# Pwdr-Circuit-0_1.net
KiCad netlist of a schematic drawn in EAGLE
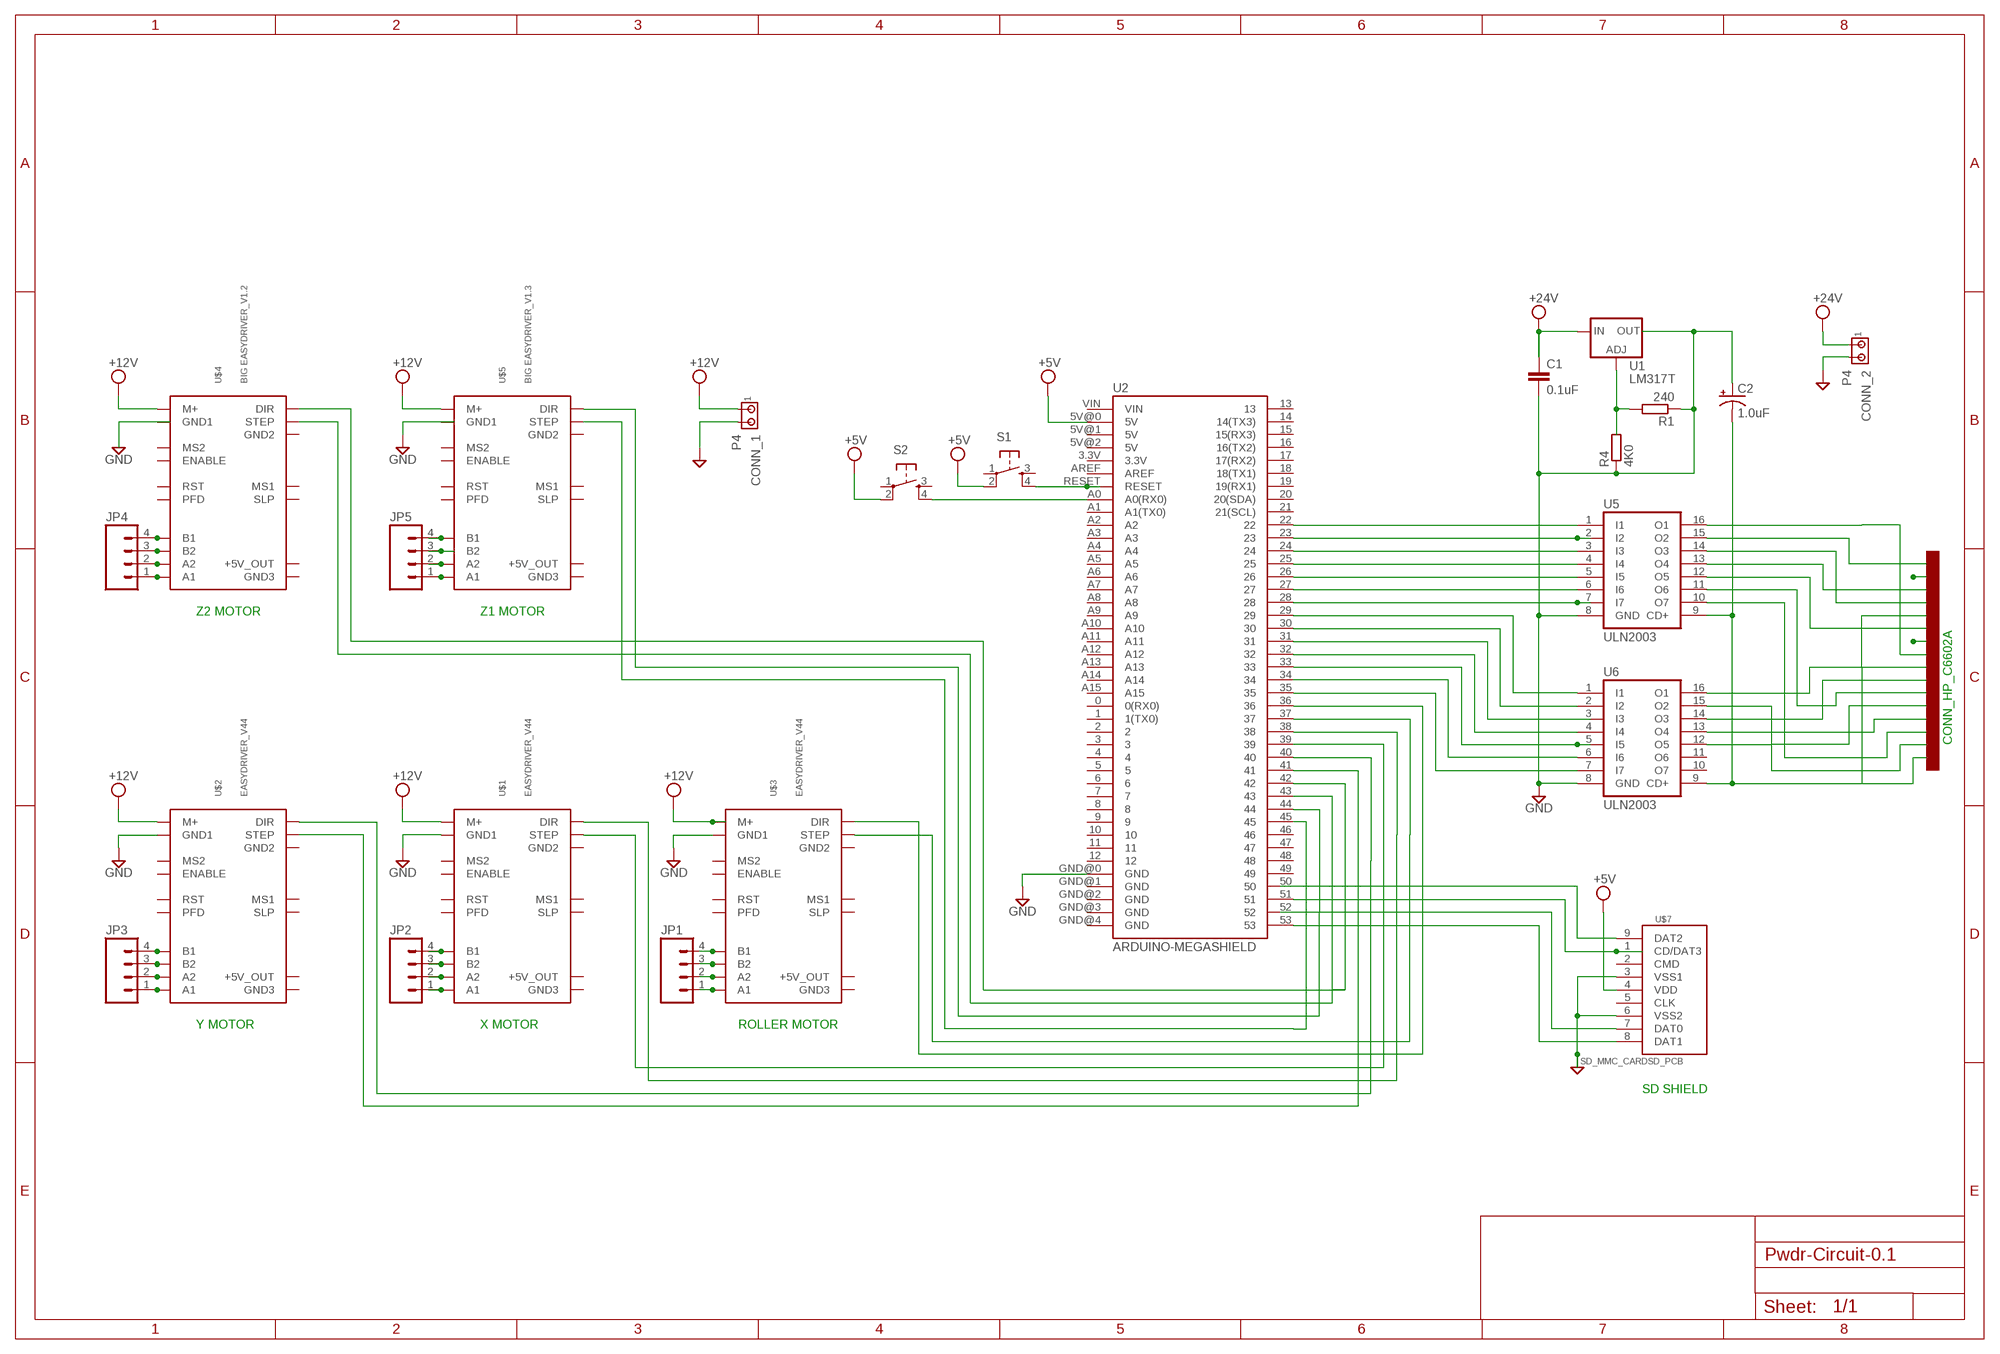
[diagram p0: schematic, sheet 1]

(export (version "E")
  (design (tool "Eeschema 10.0.6"))
  (components
    (comp (ref "C1")
      (value "0.1uF")
      (footprint "eagle-import:C025-024X044")
      (libsource (lib "eagle-import") (part "C-EU025-024X044"))
    )
    (comp (ref "C2")
      (value "1.0uF")
      (footprint "eagle-import:085CS_1AR")
      (libsource (lib "eagle-import") (part "CPOL-US085CS-1AR"))
    )
    (comp (ref "CONN_1")
      (value "P4")
      (footprint "eagle-import:1X2MTA")
      (libsource (lib "eagle-import") (part "MTA02-156"))
    )
    (comp (ref "CONN_2")
      (value "P4")
      (footprint "eagle-import:1X2MTA")
      (libsource (lib "eagle-import") (part "MTA02-156"))
    )
    (comp (ref "JP1")
      (value "M041X04_NO_SILK")
      (footprint "eagle-import:1X04_NO_SILK")
      (libsource (lib "eagle-import") (part "M041X04_NO_SILK"))
    )
    (comp (ref "JP2")
      (value "M041X04_NO_SILK")
      (footprint "eagle-import:1X04_NO_SILK")
      (libsource (lib "eagle-import") (part "M041X04_NO_SILK"))
    )
    (comp (ref "JP3")
      (value "M041X04_NO_SILK")
      (footprint "eagle-import:1X04_NO_SILK")
      (libsource (lib "eagle-import") (part "M041X04_NO_SILK"))
    )
    (comp (ref "JP4")
      (value "M041X04_NO_SILK")
      (footprint "eagle-import:1X04_NO_SILK")
      (libsource (lib "eagle-import") (part "M041X04_NO_SILK"))
    )
    (comp (ref "JP5")
      (value "M041X04_NO_SILK")
      (footprint "eagle-import:1X04_NO_SILK")
      (libsource (lib "eagle-import") (part "M041X04_NO_SILK"))
    )
    (comp (ref "R1")
      (value "240")
      (footprint "eagle-import:0204V")
      (libsource (lib "eagle-import") (part "R-EU_0204/2V"))
    )
    (comp (ref "R4")
      (value "4K0")
      (footprint "eagle-import:0204V")
      (libsource (lib "eagle-import") (part "R-EU_0204/2V"))
    )
    (comp (ref "S1")
      (value "TAC_SWITCHSMD")
      (footprint "eagle-import:TACTILE_SWITCH_SMD")
      (libsource (lib "eagle-import") (part "TAC_SWITCHSMD"))
    )
    (comp (ref "S2")
      (value "TAC_SWITCHSMD")
      (footprint "eagle-import:TACTILE_SWITCH_SMD")
      (libsource (lib "eagle-import") (part "TAC_SWITCHSMD"))
    )
    (comp (ref "U$1")
      (value "EASYDRIVER_V44")
      (footprint "eagle-import:EASYDRIVER_V44")
      (libsource (lib "eagle-import") (part "EASYDRIVER_V44"))
    )
    (comp (ref "U$2")
      (value "EASYDRIVER_V44")
      (footprint "eagle-import:EASYDRIVER_V44")
      (libsource (lib "eagle-import") (part "EASYDRIVER_V44"))
    )
    (comp (ref "U$3")
      (value "EASYDRIVER_V44")
      (footprint "eagle-import:EASYDRIVER_V44")
      (libsource (lib "eagle-import") (part "EASYDRIVER_V44"))
    )
    (comp (ref "U$4")
      (value "BIG EASYDRIVER_V1.2")
      (footprint "eagle-import:EASYDRIVER_V44")
      (libsource (lib "eagle-import") (part "EASYDRIVER_V44"))
    )
    (comp (ref "U$5")
      (value "BIG EASYDRIVER_V1.3")
      (footprint "eagle-import:EASYDRIVER_V44")
      (libsource (lib "eagle-import") (part "EASYDRIVER_V44"))
    )
    (comp (ref "U$7")
      (value "SD_MMC_CARDSD_PCB")
      (footprint "eagle-import:SD-MMC-CARD")
      (libsource (lib "eagle-import") (part "SD_MMC_CARDSD_PCB"))
    )
    (comp (ref "U1")
      (value "LM317T")
      (footprint "eagle-import:317L")
      (libsource (lib "eagle-import") (part "LM317L"))
    )
    (comp (ref "U2")
      (value "ARDUINO-MEGASHIELD")
      (footprint "eagle-import:ARDUINO_MEGA")
      (libsource (lib "eagle-import") (part "ARDUINO-MEGAFULL"))
    )
    (comp (ref "U5")
      (value "ULN2003")
      (footprint "eagle-import:DIL16")
      (libsource (lib "eagle-import") (part "ULN2003AN"))
    )
    (comp (ref "U6")
      (value "ULN2003")
      (footprint "eagle-import:DIL16")
      (libsource (lib "eagle-import") (part "ULN2003AN"))
    )
  )
  (nets
    (net (code "1") (name "+12V") (class "Default")
      (node (ref "C1") (pin "1") (pinfunction "1_1") (pintype "passive"))
      (node (ref "CONN_1") (pin "1") (pinfunction "1_1") (pintype "passive"))
      (node (ref "CONN_2") (pin "1") (pinfunction "1_1") (pintype "passive"))
      (node (ref "S1") (pin "2") (pinfunction "2_2") (pintype "passive"))
      (node (ref "S2") (pin "2") (pinfunction "2_2") (pintype "passive"))
      (node (ref "U$1") (pin "M+") (pinfunction "M+_M+") (pintype "bidirectional"))
      (node (ref "U$2") (pin "M+") (pinfunction "M+_M+") (pintype "bidirectional"))
      (node (ref "U$3") (pin "M+") (pinfunction "M+_M+") (pintype "bidirectional"))
      (node (ref "U$4") (pin "M+") (pinfunction "M+_M+") (pintype "bidirectional"))
      (node (ref "U$5") (pin "M+") (pinfunction "M+_M+") (pintype "bidirectional"))
      (node (ref "U$7") (pin "4") (pinfunction "VDD_4") (pintype "bidirectional"))
      (node (ref "U1") (pin "3") (pinfunction "IN_3") (pintype "input"))
      (node (ref "U2") (pin "5V@0") (pinfunction "5V_5V@0") (pintype "bidirectional"))
    )
    (net (code "2") (name "AGND") (class "Default")
      (node (ref "C1") (pin "2") (pinfunction "2_2") (pintype "passive"))
      (node (ref "C2") (pin "+") (pinfunction "+_+") (pintype "passive"))
      (node (ref "CONN_1") (pin "2") (pinfunction "2_2") (pintype "passive"))
      (node (ref "CONN_2") (pin "2") (pinfunction "2_2") (pintype "passive"))
      (node (ref "R1") (pin "1") (pinfunction "1_1") (pintype "passive"))
      (node (ref "R4") (pin "1") (pinfunction "1_1") (pintype "passive"))
      (node (ref "U$1") (pin "GND1") (pinfunction "GND1_GND1") (pintype "bidirectional"))
      (node (ref "U$2") (pin "GND1") (pinfunction "GND1_GND1") (pintype "bidirectional"))
      (node (ref "U$3") (pin "GND1") (pinfunction "GND1_GND1") (pintype "bidirectional"))
      (node (ref "U$4") (pin "GND1") (pinfunction "GND1_GND1") (pintype "bidirectional"))
      (node (ref "U$5") (pin "GND1") (pinfunction "GND1_GND1") (pintype "bidirectional"))
      (node (ref "U$7") (pin "3") (pinfunction "VSS1_3") (pintype "bidirectional"))
      (node (ref "U$7") (pin "6") (pinfunction "VSS2_6") (pintype "bidirectional"))
      (node (ref "U1") (pin "2") (pinfunction "OUT_2") (pintype "passive"))
      (node (ref "U2") (pin "GND@0") (pinfunction "GND_GND@0") (pintype "bidirectional"))
      (node (ref "U5") (pin "8") (pinfunction "GND_8") (pintype "power_in"))
      (node (ref "U6") (pin "8") (pinfunction "GND_8") (pintype "power_in"))
    )
    (net (code "3") (name "Net-(JP1-Pad1)") (class "Default")
      (node (ref "JP1") (pin "1") (pinfunction "1_1") (pintype "passive"))
      (node (ref "U$3") (pin "A1") (pinfunction "A1_A1") (pintype "bidirectional"))
    )
    (net (code "4") (name "Net-(JP1-Pad2)") (class "Default")
      (node (ref "JP1") (pin "2") (pinfunction "2_2") (pintype "passive"))
      (node (ref "U$3") (pin "A2") (pinfunction "A2_A2") (pintype "bidirectional"))
    )
    (net (code "5") (name "Net-(JP1-Pad3)") (class "Default")
      (node (ref "JP1") (pin "3") (pinfunction "3_3") (pintype "passive"))
      (node (ref "U$3") (pin "B2") (pinfunction "B2_B2") (pintype "bidirectional"))
    )
    (net (code "6") (name "Net-(JP1-Pad4)") (class "Default")
      (node (ref "JP1") (pin "4") (pinfunction "4_4") (pintype "passive"))
      (node (ref "U$3") (pin "B1") (pinfunction "B1_B1") (pintype "bidirectional"))
    )
    (net (code "7") (name "Net-(JP2-Pad1)") (class "Default")
      (node (ref "JP2") (pin "1") (pinfunction "1_1") (pintype "passive"))
      (node (ref "U$1") (pin "A1") (pinfunction "A1_A1") (pintype "bidirectional"))
    )
    (net (code "8") (name "Net-(JP2-Pad2)") (class "Default")
      (node (ref "JP2") (pin "2") (pinfunction "2_2") (pintype "passive"))
      (node (ref "U$1") (pin "A2") (pinfunction "A2_A2") (pintype "bidirectional"))
    )
    (net (code "9") (name "Net-(JP2-Pad3)") (class "Default")
      (node (ref "JP2") (pin "3") (pinfunction "3_3") (pintype "passive"))
      (node (ref "U$1") (pin "B2") (pinfunction "B2_B2") (pintype "bidirectional"))
    )
    (net (code "10") (name "Net-(JP2-Pad4)") (class "Default")
      (node (ref "JP2") (pin "4") (pinfunction "4_4") (pintype "passive"))
      (node (ref "U$1") (pin "B1") (pinfunction "B1_B1") (pintype "bidirectional"))
    )
    (net (code "11") (name "Net-(JP3-Pad1)") (class "Default")
      (node (ref "JP3") (pin "1") (pinfunction "1_1") (pintype "passive"))
      (node (ref "U$2") (pin "A1") (pinfunction "A1_A1") (pintype "bidirectional"))
    )
    (net (code "12") (name "Net-(JP3-Pad2)") (class "Default")
      (node (ref "JP3") (pin "2") (pinfunction "2_2") (pintype "passive"))
      (node (ref "U$2") (pin "A2") (pinfunction "A2_A2") (pintype "bidirectional"))
    )
    (net (code "13") (name "Net-(JP3-Pad3)") (class "Default")
      (node (ref "JP3") (pin "3") (pinfunction "3_3") (pintype "passive"))
      (node (ref "U$2") (pin "B2") (pinfunction "B2_B2") (pintype "bidirectional"))
    )
    (net (code "14") (name "Net-(JP3-Pad4)") (class "Default")
      (node (ref "JP3") (pin "4") (pinfunction "4_4") (pintype "passive"))
      (node (ref "U$2") (pin "B1") (pinfunction "B1_B1") (pintype "bidirectional"))
    )
    (net (code "15") (name "Net-(JP4-Pad1)") (class "Default")
      (node (ref "JP4") (pin "1") (pinfunction "1_1") (pintype "passive"))
      (node (ref "U$4") (pin "A1") (pinfunction "A1_A1") (pintype "bidirectional"))
    )
    (net (code "16") (name "Net-(JP4-Pad2)") (class "Default")
      (node (ref "JP4") (pin "2") (pinfunction "2_2") (pintype "passive"))
      (node (ref "U$4") (pin "A2") (pinfunction "A2_A2") (pintype "bidirectional"))
    )
    (net (code "17") (name "Net-(JP4-Pad3)") (class "Default")
      (node (ref "JP4") (pin "3") (pinfunction "3_3") (pintype "passive"))
      (node (ref "U$4") (pin "B2") (pinfunction "B2_B2") (pintype "bidirectional"))
    )
    (net (code "18") (name "Net-(JP4-Pad4)") (class "Default")
      (node (ref "JP4") (pin "4") (pinfunction "4_4") (pintype "passive"))
      (node (ref "U$4") (pin "B1") (pinfunction "B1_B1") (pintype "bidirectional"))
    )
    (net (code "19") (name "Net-(JP5-Pad1)") (class "Default")
      (node (ref "JP5") (pin "1") (pinfunction "1_1") (pintype "passive"))
      (node (ref "U$5") (pin "A1") (pinfunction "A1_A1") (pintype "bidirectional"))
    )
    (net (code "20") (name "Net-(JP5-Pad2)") (class "Default")
      (node (ref "JP5") (pin "2") (pinfunction "2_2") (pintype "passive"))
      (node (ref "U$5") (pin "A2") (pinfunction "A2_A2") (pintype "bidirectional"))
    )
    (net (code "21") (name "Net-(JP5-Pad3)") (class "Default")
      (node (ref "JP5") (pin "3") (pinfunction "3_3") (pintype "passive"))
      (node (ref "U$5") (pin "B2") (pinfunction "B2_B2") (pintype "bidirectional"))
    )
    (net (code "22") (name "Net-(JP5-Pad4)") (class "Default")
      (node (ref "JP5") (pin "4") (pinfunction "4_4") (pintype "passive"))
      (node (ref "U$5") (pin "B1") (pinfunction "B1_B1") (pintype "bidirectional"))
    )
    (net (code "23") (name "Net-(S1-Pad4)") (class "Default")
      (node (ref "S1") (pin "4") (pinfunction "4_4") (pintype "passive"))
      (node (ref "U2") (pin "RESET") (pinfunction "RESET_RESET") (pintype "bidirectional"))
    )
    (net (code "24") (name "Net-(U$1-PadDIR)") (class "Default")
      (node (ref "U$1") (pin "DIR") (pinfunction "DIR_DIR") (pintype "bidirectional"))
      (node (ref "U$2") (pin "DIR") (pinfunction "DIR_DIR") (pintype "bidirectional"))
      (node (ref "U2") (pin "38") (pinfunction "38_38") (pintype "bidirectional"))
      (node (ref "U2") (pin "40") (pinfunction "40_40") (pintype "bidirectional"))
    )
    (net (code "25") (name "Net-(U$1-PadSTEP)") (class "Default")
      (node (ref "U$1") (pin "STEP") (pinfunction "STEP_STEP") (pintype "bidirectional"))
      (node (ref "U2") (pin "39") (pinfunction "39_39") (pintype "bidirectional"))
    )
    (net (code "26") (name "Net-(U$2-PadSTEP)") (class "Default")
      (node (ref "U$2") (pin "STEP") (pinfunction "STEP_STEP") (pintype "bidirectional"))
      (node (ref "U2") (pin "41") (pinfunction "41_41") (pintype "bidirectional"))
    )
    (net (code "27") (name "Net-(U$3-PadDIR)") (class "Default")
      (node (ref "U$3") (pin "DIR") (pinfunction "DIR_DIR") (pintype "bidirectional"))
      (node (ref "U2") (pin "36") (pinfunction "36_36") (pintype "bidirectional"))
    )
    (net (code "28") (name "Net-(U$3-PadSTEP)") (class "Default")
      (node (ref "U$3") (pin "STEP") (pinfunction "STEP_STEP") (pintype "bidirectional"))
      (node (ref "U2") (pin "37") (pinfunction "37_37") (pintype "bidirectional"))
    )
    (net (code "29") (name "Net-(U$4-PadDIR)") (class "Default")
      (node (ref "U$4") (pin "DIR") (pinfunction "DIR_DIR") (pintype "bidirectional"))
      (node (ref "U2") (pin "42") (pinfunction "42_42") (pintype "bidirectional"))
    )
    (net (code "30") (name "Net-(U$4-PadSTEP)") (class "Default")
      (node (ref "U$4") (pin "STEP") (pinfunction "STEP_STEP") (pintype "bidirectional"))
      (node (ref "U2") (pin "43") (pinfunction "43_43") (pintype "bidirectional"))
    )
    (net (code "31") (name "Net-(U$5-PadDIR)") (class "Default")
      (node (ref "U$5") (pin "DIR") (pinfunction "DIR_DIR") (pintype "bidirectional"))
      (node (ref "U2") (pin "44") (pinfunction "44_44") (pintype "bidirectional"))
    )
    (net (code "32") (name "Net-(U$5-PadSTEP)") (class "Default")
      (node (ref "U$5") (pin "STEP") (pinfunction "STEP_STEP") (pintype "bidirectional"))
      (node (ref "U2") (pin "45") (pinfunction "45_45") (pintype "bidirectional"))
    )
    (net (code "33") (name "Net-(U$7-CD{slash}DAT3)") (class "Default")
      (node (ref "U$7") (pin "1") (pinfunction "CD/DAT3_1") (pintype "bidirectional"))
      (node (ref "U2") (pin "51") (pinfunction "51_51") (pintype "bidirectional"))
    )
    (net (code "34") (name "Net-(U$7-DAT1)") (class "Default")
      (node (ref "U$7") (pin "8") (pinfunction "DAT1_8") (pintype "bidirectional"))
      (node (ref "U2") (pin "53") (pinfunction "53_53") (pintype "bidirectional"))
    )
    (net (code "35") (name "Net-(U1-ADJ)") (class "Default")
      (node (ref "R1") (pin "2") (pinfunction "2_2") (pintype "passive"))
      (node (ref "R4") (pin "2") (pinfunction "2_2") (pintype "passive"))
      (node (ref "U1") (pin "1") (pinfunction "ADJ_1") (pintype "input"))
    )
    (net (code "36") (name "Net-(U2-A0(RX0))") (class "Default")
      (node (ref "S2") (pin "4") (pinfunction "4_4") (pintype "passive"))
      (node (ref "U2") (pin "A0") (pinfunction "A0(RX0)_A0") (pintype "bidirectional"))
    )
    (net (code "37") (name "Net-(U5-CD+)") (class "Default")
      (node (ref "C2") (pin "-") (pinfunction "-_-") (pintype "passive"))
      (node (ref "U5") (pin "9") (pinfunction "CD+_9") (pintype "passive"))
      (node (ref "U6") (pin "9") (pinfunction "CD+_9") (pintype "passive"))
    )
    (net (code "38") (name "Net-(U5-I1)") (class "Default")
      (node (ref "U2") (pin "22") (pinfunction "22_22") (pintype "bidirectional"))
      (node (ref "U5") (pin "1") (pinfunction "I1_1") (pintype "input"))
    )
    (net (code "39") (name "Net-(U5-I2)") (class "Default")
      (node (ref "U2") (pin "23") (pinfunction "23_23") (pintype "bidirectional"))
      (node (ref "U5") (pin "2") (pinfunction "I2_2") (pintype "input"))
    )
    (net (code "40") (name "Net-(U5-I3)") (class "Default")
      (node (ref "U2") (pin "24") (pinfunction "24_24") (pintype "bidirectional"))
      (node (ref "U5") (pin "3") (pinfunction "I3_3") (pintype "input"))
    )
    (net (code "41") (name "Net-(U5-I4)") (class "Default")
      (node (ref "U2") (pin "25") (pinfunction "25_25") (pintype "bidirectional"))
      (node (ref "U5") (pin "4") (pinfunction "I4_4") (pintype "input"))
    )
    (net (code "42") (name "Net-(U5-I5)") (class "Default")
      (node (ref "U2") (pin "26") (pinfunction "26_26") (pintype "bidirectional"))
      (node (ref "U5") (pin "5") (pinfunction "I5_5") (pintype "input"))
    )
    (net (code "43") (name "Net-(U5-I6)") (class "Default")
      (node (ref "U2") (pin "27") (pinfunction "27_27") (pintype "bidirectional"))
      (node (ref "U5") (pin "6") (pinfunction "I6_6") (pintype "input"))
    )
    (net (code "44") (name "Net-(U5-I7)") (class "Default")
      (node (ref "U2") (pin "28") (pinfunction "28_28") (pintype "bidirectional"))
      (node (ref "U5") (pin "7") (pinfunction "I7_7") (pintype "input"))
    )
    (net (code "45") (name "Net-(U6-I1)") (class "Default")
      (node (ref "U2") (pin "29") (pinfunction "29_29") (pintype "bidirectional"))
      (node (ref "U6") (pin "1") (pinfunction "I1_1") (pintype "input"))
    )
    (net (code "46") (name "Net-(U6-I2)") (class "Default")
      (node (ref "U2") (pin "30") (pinfunction "30_30") (pintype "bidirectional"))
      (node (ref "U6") (pin "2") (pinfunction "I2_2") (pintype "input"))
    )
    (net (code "47") (name "Net-(U6-I3)") (class "Default")
      (node (ref "U2") (pin "31") (pinfunction "31_31") (pintype "bidirectional"))
      (node (ref "U6") (pin "3") (pinfunction "I3_3") (pintype "input"))
    )
    (net (code "48") (name "Net-(U6-I4)") (class "Default")
      (node (ref "U2") (pin "32") (pinfunction "32_32") (pintype "bidirectional"))
      (node (ref "U6") (pin "4") (pinfunction "I4_4") (pintype "input"))
    )
    (net (code "49") (name "Net-(U6-I5)") (class "Default")
      (node (ref "U2") (pin "33") (pinfunction "33_33") (pintype "bidirectional"))
      (node (ref "U6") (pin "5") (pinfunction "I5_5") (pintype "input"))
    )
    (net (code "50") (name "Net-(U6-I6)") (class "Default")
      (node (ref "U2") (pin "34") (pinfunction "34_34") (pintype "bidirectional"))
      (node (ref "U6") (pin "6") (pinfunction "I6_6") (pintype "input"))
    )
    (net (code "51") (name "Net-(U6-I7)") (class "Default")
      (node (ref "U2") (pin "35") (pinfunction "35_35") (pintype "bidirectional"))
      (node (ref "U6") (pin "7") (pinfunction "I7_7") (pintype "input"))
    )
    (net (code "52") (name "unconnected-(S1-Pad1)") (class "Default")
      (node (ref "S1") (pin "1") (pinfunction "1_1") (pintype "passive"))
    )
    (net (code "53") (name "unconnected-(S1-Pad3)") (class "Default")
      (node (ref "S1") (pin "3") (pinfunction "3_3") (pintype "passive"))
    )
    (net (code "54") (name "unconnected-(S2-Pad1)") (class "Default")
      (node (ref "S2") (pin "1") (pinfunction "1_1") (pintype "passive"))
    )
    (net (code "55") (name "unconnected-(S2-Pad3)") (class "Default")
      (node (ref "S2") (pin "3") (pinfunction "3_3") (pintype "passive"))
    )
    (net (code "56") (name "unconnected-(U$1-+5V_OUT-PadP$11)") (class "Default")
      (node (ref "U$1") (pin "P$11") (pinfunction "+5V_OUT_P$11") (pintype "bidirectional"))
    )
    (net (code "57") (name "unconnected-(U$1-PadENABLE)") (class "Default")
      (node (ref "U$1") (pin "ENABLE") (pinfunction "ENABLE_ENABLE") (pintype "bidirectional"))
    )
    (net (code "58") (name "unconnected-(U$1-PadGND2)") (class "Default")
      (node (ref "U$1") (pin "GND2") (pinfunction "GND2_GND2") (pintype "bidirectional"))
    )
    (net (code "59") (name "unconnected-(U$1-PadGND3)") (class "Default")
      (node (ref "U$1") (pin "GND3") (pinfunction "GND3_GND3") (pintype "bidirectional"))
    )
    (net (code "60") (name "unconnected-(U$1-PadMS1)") (class "Default")
      (node (ref "U$1") (pin "MS1") (pinfunction "MS1_MS1") (pintype "bidirectional"))
    )
    (net (code "61") (name "unconnected-(U$1-PadMS2)") (class "Default")
      (node (ref "U$1") (pin "MS2") (pinfunction "MS2_MS2") (pintype "bidirectional"))
    )
    (net (code "62") (name "unconnected-(U$1-PadPFD)") (class "Default")
      (node (ref "U$1") (pin "PFD") (pinfunction "PFD_PFD") (pintype "bidirectional"))
    )
    (net (code "63") (name "unconnected-(U$1-PadRST)") (class "Default")
      (node (ref "U$1") (pin "RST") (pinfunction "RST_RST") (pintype "bidirectional"))
    )
    (net (code "64") (name "unconnected-(U$1-SLP-PadSLEEP)") (class "Default")
      (node (ref "U$1") (pin "SLEEP") (pinfunction "SLP_SLEEP") (pintype "bidirectional"))
    )
    (net (code "65") (name "unconnected-(U$2-+5V_OUT-PadP$11)") (class "Default")
      (node (ref "U$2") (pin "P$11") (pinfunction "+5V_OUT_P$11") (pintype "bidirectional"))
    )
    (net (code "66") (name "unconnected-(U$2-PadENABLE)") (class "Default")
      (node (ref "U$2") (pin "ENABLE") (pinfunction "ENABLE_ENABLE") (pintype "bidirectional"))
    )
    (net (code "67") (name "unconnected-(U$2-PadGND2)") (class "Default")
      (node (ref "U$2") (pin "GND2") (pinfunction "GND2_GND2") (pintype "bidirectional"))
    )
    (net (code "68") (name "unconnected-(U$2-PadGND3)") (class "Default")
      (node (ref "U$2") (pin "GND3") (pinfunction "GND3_GND3") (pintype "bidirectional"))
    )
    (net (code "69") (name "unconnected-(U$2-PadMS1)") (class "Default")
      (node (ref "U$2") (pin "MS1") (pinfunction "MS1_MS1") (pintype "bidirectional"))
    )
    (net (code "70") (name "unconnected-(U$2-PadMS2)") (class "Default")
      (node (ref "U$2") (pin "MS2") (pinfunction "MS2_MS2") (pintype "bidirectional"))
    )
    (net (code "71") (name "unconnected-(U$2-PadPFD)") (class "Default")
      (node (ref "U$2") (pin "PFD") (pinfunction "PFD_PFD") (pintype "bidirectional"))
    )
    (net (code "72") (name "unconnected-(U$2-PadRST)") (class "Default")
      (node (ref "U$2") (pin "RST") (pinfunction "RST_RST") (pintype "bidirectional"))
    )
    (net (code "73") (name "unconnected-(U$2-SLP-PadSLEEP)") (class "Default")
      (node (ref "U$2") (pin "SLEEP") (pinfunction "SLP_SLEEP") (pintype "bidirectional"))
    )
    (net (code "74") (name "unconnected-(U$3-+5V_OUT-PadP$11)") (class "Default")
      (node (ref "U$3") (pin "P$11") (pinfunction "+5V_OUT_P$11") (pintype "bidirectional"))
    )
    (net (code "75") (name "unconnected-(U$3-PadENABLE)") (class "Default")
      (node (ref "U$3") (pin "ENABLE") (pinfunction "ENABLE_ENABLE") (pintype "bidirectional"))
    )
    (net (code "76") (name "unconnected-(U$3-PadGND2)") (class "Default")
      (node (ref "U$3") (pin "GND2") (pinfunction "GND2_GND2") (pintype "bidirectional"))
    )
    (net (code "77") (name "unconnected-(U$3-PadGND3)") (class "Default")
      (node (ref "U$3") (pin "GND3") (pinfunction "GND3_GND3") (pintype "bidirectional"))
    )
    (net (code "78") (name "unconnected-(U$3-PadMS1)") (class "Default")
      (node (ref "U$3") (pin "MS1") (pinfunction "MS1_MS1") (pintype "bidirectional"))
    )
    (net (code "79") (name "unconnected-(U$3-PadMS2)") (class "Default")
      (node (ref "U$3") (pin "MS2") (pinfunction "MS2_MS2") (pintype "bidirectional"))
    )
    (net (code "80") (name "unconnected-(U$3-PadPFD)") (class "Default")
      (node (ref "U$3") (pin "PFD") (pinfunction "PFD_PFD") (pintype "bidirectional"))
    )
    (net (code "81") (name "unconnected-(U$3-PadRST)") (class "Default")
      (node (ref "U$3") (pin "RST") (pinfunction "RST_RST") (pintype "bidirectional"))
    )
    (net (code "82") (name "unconnected-(U$3-SLP-PadSLEEP)") (class "Default")
      (node (ref "U$3") (pin "SLEEP") (pinfunction "SLP_SLEEP") (pintype "bidirectional"))
    )
    (net (code "83") (name "unconnected-(U$4-+5V_OUT-PadP$11)") (class "Default")
      (node (ref "U$4") (pin "P$11") (pinfunction "+5V_OUT_P$11") (pintype "bidirectional"))
    )
    (net (code "84") (name "unconnected-(U$4-PadENABLE)") (class "Default")
      (node (ref "U$4") (pin "ENABLE") (pinfunction "ENABLE_ENABLE") (pintype "bidirectional"))
    )
    (net (code "85") (name "unconnected-(U$4-PadGND2)") (class "Default")
      (node (ref "U$4") (pin "GND2") (pinfunction "GND2_GND2") (pintype "bidirectional"))
    )
    (net (code "86") (name "unconnected-(U$4-PadGND3)") (class "Default")
      (node (ref "U$4") (pin "GND3") (pinfunction "GND3_GND3") (pintype "bidirectional"))
    )
    (net (code "87") (name "unconnected-(U$4-PadMS1)") (class "Default")
      (node (ref "U$4") (pin "MS1") (pinfunction "MS1_MS1") (pintype "bidirectional"))
    )
    (net (code "88") (name "unconnected-(U$4-PadMS2)") (class "Default")
      (node (ref "U$4") (pin "MS2") (pinfunction "MS2_MS2") (pintype "bidirectional"))
    )
    (net (code "89") (name "unconnected-(U$4-PadPFD)") (class "Default")
      (node (ref "U$4") (pin "PFD") (pinfunction "PFD_PFD") (pintype "bidirectional"))
    )
    (net (code "90") (name "unconnected-(U$4-PadRST)") (class "Default")
      (node (ref "U$4") (pin "RST") (pinfunction "RST_RST") (pintype "bidirectional"))
    )
    (net (code "91") (name "unconnected-(U$4-SLP-PadSLEEP)") (class "Default")
      (node (ref "U$4") (pin "SLEEP") (pinfunction "SLP_SLEEP") (pintype "bidirectional"))
    )
    (net (code "92") (name "unconnected-(U$5-+5V_OUT-PadP$11)") (class "Default")
      (node (ref "U$5") (pin "P$11") (pinfunction "+5V_OUT_P$11") (pintype "bidirectional"))
    )
    (net (code "93") (name "unconnected-(U$5-PadENABLE)") (class "Default")
      (node (ref "U$5") (pin "ENABLE") (pinfunction "ENABLE_ENABLE") (pintype "bidirectional"))
    )
    (net (code "94") (name "unconnected-(U$5-PadGND2)") (class "Default")
      (node (ref "U$5") (pin "GND2") (pinfunction "GND2_GND2") (pintype "bidirectional"))
    )
    (net (code "95") (name "unconnected-(U$5-PadGND3)") (class "Default")
      (node (ref "U$5") (pin "GND3") (pinfunction "GND3_GND3") (pintype "bidirectional"))
    )
    (net (code "96") (name "unconnected-(U$5-PadMS1)") (class "Default")
      (node (ref "U$5") (pin "MS1") (pinfunction "MS1_MS1") (pintype "bidirectional"))
    )
    (net (code "97") (name "unconnected-(U$5-PadMS2)") (class "Default")
      (node (ref "U$5") (pin "MS2") (pinfunction "MS2_MS2") (pintype "bidirectional"))
    )
    (net (code "98") (name "unconnected-(U$5-PadPFD)") (class "Default")
      (node (ref "U$5") (pin "PFD") (pinfunction "PFD_PFD") (pintype "bidirectional"))
    )
    (net (code "99") (name "unconnected-(U$5-PadRST)") (class "Default")
      (node (ref "U$5") (pin "RST") (pinfunction "RST_RST") (pintype "bidirectional"))
    )
    (net (code "100") (name "unconnected-(U$5-SLP-PadSLEEP)") (class "Default")
      (node (ref "U$5") (pin "SLEEP") (pinfunction "SLP_SLEEP") (pintype "bidirectional"))
    )
    (net (code "101") (name "unconnected-(U$7-CLK-Pad5)") (class "Default")
      (node (ref "U$7") (pin "5") (pinfunction "CLK_5") (pintype "bidirectional"))
    )
    (net (code "102") (name "unconnected-(U$7-CMD-Pad2)") (class "Default")
      (node (ref "U$7") (pin "2") (pinfunction "CMD_2") (pintype "bidirectional"))
    )
    (net (code "103") (name "unconnected-(U$7-DAT0-Pad7)") (class "Default")
      (node (ref "U$7") (pin "7") (pinfunction "DAT0_7") (pintype "bidirectional"))
    )
    (net (code "104") (name "unconnected-(U$7-DAT2-Pad9)") (class "Default")
      (node (ref "U$7") (pin "9") (pinfunction "DAT2_9") (pintype "bidirectional"))
    )
    (net (code "105") (name "unconnected-(U2-0(RX0)-Pad0)") (class "Default")
      (node (ref "U2") (pin "0") (pinfunction "0(RX0)_0") (pintype "bidirectional"))
    )
    (net (code "106") (name "unconnected-(U2-1(TX0)-Pad1)") (class "Default")
      (node (ref "U2") (pin "1") (pinfunction "1(TX0)_1") (pintype "bidirectional"))
    )
    (net (code "107") (name "unconnected-(U2-5V-Pad5V@1)") (class "Default")
      (node (ref "U2") (pin "5V@1") (pinfunction "5V_5V@1") (pintype "bidirectional"))
    )
    (net (code "108") (name "unconnected-(U2-5V-Pad5V@2)") (class "Default")
      (node (ref "U2") (pin "5V@2") (pinfunction "5V_5V@2") (pintype "bidirectional"))
    )
    (net (code "109") (name "unconnected-(U2-14(TX3)-Pad14)") (class "Default")
      (node (ref "U2") (pin "14") (pinfunction "14(TX3)_14") (pintype "bidirectional"))
    )
    (net (code "110") (name "unconnected-(U2-15(RX3)-Pad15)") (class "Default")
      (node (ref "U2") (pin "15") (pinfunction "15(RX3)_15") (pintype "bidirectional"))
    )
    (net (code "111") (name "unconnected-(U2-16(TX2)-Pad16)") (class "Default")
      (node (ref "U2") (pin "16") (pinfunction "16(TX2)_16") (pintype "bidirectional"))
    )
    (net (code "112") (name "unconnected-(U2-17(RX2)-Pad17)") (class "Default")
      (node (ref "U2") (pin "17") (pinfunction "17(RX2)_17") (pintype "bidirectional"))
    )
    (net (code "113") (name "unconnected-(U2-18(TX1)-Pad18)") (class "Default")
      (node (ref "U2") (pin "18") (pinfunction "18(TX1)_18") (pintype "bidirectional"))
    )
    (net (code "114") (name "unconnected-(U2-19(RX1)-Pad19)") (class "Default")
      (node (ref "U2") (pin "19") (pinfunction "19(RX1)_19") (pintype "bidirectional"))
    )
    (net (code "115") (name "unconnected-(U2-20(SDA)-Pad20)") (class "Default")
      (node (ref "U2") (pin "20") (pinfunction "20(SDA)_20") (pintype "bidirectional"))
    )
    (net (code "116") (name "unconnected-(U2-21(SCL)-Pad21)") (class "Default")
      (node (ref "U2") (pin "21") (pinfunction "21(SCL)_21") (pintype "bidirectional"))
    )
    (net (code "117") (name "unconnected-(U2-A1(TX0)-PadA1)") (class "Default")
      (node (ref "U2") (pin "A1") (pinfunction "A1(TX0)_A1") (pintype "bidirectional"))
    )
    (net (code "118") (name "unconnected-(U2-GND-PadGND@1)") (class "Default")
      (node (ref "U2") (pin "GND@1") (pinfunction "GND_GND@1") (pintype "bidirectional"))
    )
    (net (code "119") (name "unconnected-(U2-GND-PadGND@2)") (class "Default")
      (node (ref "U2") (pin "GND@2") (pinfunction "GND_GND@2") (pintype "bidirectional"))
    )
    (net (code "120") (name "unconnected-(U2-GND-PadGND@3)") (class "Default")
      (node (ref "U2") (pin "GND@3") (pinfunction "GND_GND@3") (pintype "bidirectional"))
    )
    (net (code "121") (name "unconnected-(U2-GND-PadGND@4)") (class "Default")
      (node (ref "U2") (pin "GND@4") (pinfunction "GND_GND@4") (pintype "bidirectional"))
    )
    (net (code "122") (name "unconnected-(U2-Pad2)") (class "Default")
      (node (ref "U2") (pin "2") (pinfunction "2_2") (pintype "bidirectional"))
    )
    (net (code "123") (name "unconnected-(U2-Pad3)") (class "Default")
      (node (ref "U2") (pin "3") (pinfunction "3_3") (pintype "bidirectional"))
    )
    (net (code "124") (name "unconnected-(U2-Pad3.3V)") (class "Default")
      (node (ref "U2") (pin "3.3V") (pinfunction "3.3V_3.3V") (pintype "bidirectional"))
    )
    (net (code "125") (name "unconnected-(U2-Pad4)") (class "Default")
      (node (ref "U2") (pin "4") (pinfunction "4_4") (pintype "bidirectional"))
    )
    (net (code "126") (name "unconnected-(U2-Pad5)") (class "Default")
      (node (ref "U2") (pin "5") (pinfunction "5_5") (pintype "bidirectional"))
    )
    (net (code "127") (name "unconnected-(U2-Pad6)") (class "Default")
      (node (ref "U2") (pin "6") (pinfunction "6_6") (pintype "bidirectional"))
    )
    (net (code "128") (name "unconnected-(U2-Pad7)") (class "Default")
      (node (ref "U2") (pin "7") (pinfunction "7_7") (pintype "bidirectional"))
    )
    (net (code "129") (name "unconnected-(U2-Pad8)") (class "Default")
      (node (ref "U2") (pin "8") (pinfunction "8_8") (pintype "bidirectional"))
    )
    (net (code "130") (name "unconnected-(U2-Pad9)") (class "Default")
      (node (ref "U2") (pin "9") (pinfunction "9_9") (pintype "bidirectional"))
    )
    (net (code "131") (name "unconnected-(U2-Pad10)") (class "Default")
      (node (ref "U2") (pin "10") (pinfunction "10_10") (pintype "bidirectional"))
    )
    (net (code "132") (name "unconnected-(U2-Pad11)") (class "Default")
      (node (ref "U2") (pin "11") (pinfunction "11_11") (pintype "bidirectional"))
    )
    (net (code "133") (name "unconnected-(U2-Pad12)") (class "Default")
      (node (ref "U2") (pin "12") (pinfunction "12_12") (pintype "bidirectional"))
    )
    (net (code "134") (name "unconnected-(U2-Pad13)") (class "Default")
      (node (ref "U2") (pin "13") (pinfunction "13_13") (pintype "bidirectional"))
    )
    (net (code "135") (name "unconnected-(U2-Pad46)") (class "Default")
      (node (ref "U2") (pin "46") (pinfunction "46_46") (pintype "bidirectional"))
    )
    (net (code "136") (name "unconnected-(U2-Pad47)") (class "Default")
      (node (ref "U2") (pin "47") (pinfunction "47_47") (pintype "bidirectional"))
    )
    (net (code "137") (name "unconnected-(U2-Pad48)") (class "Default")
      (node (ref "U2") (pin "48") (pinfunction "48_48") (pintype "bidirectional"))
    )
    (net (code "138") (name "unconnected-(U2-Pad49)") (class "Default")
      (node (ref "U2") (pin "49") (pinfunction "49_49") (pintype "bidirectional"))
    )
    (net (code "139") (name "unconnected-(U2-Pad50)") (class "Default")
      (node (ref "U2") (pin "50") (pinfunction "50_50") (pintype "bidirectional"))
    )
    (net (code "140") (name "unconnected-(U2-Pad52)") (class "Default")
      (node (ref "U2") (pin "52") (pinfunction "52_52") (pintype "bidirectional"))
    )
    (net (code "141") (name "unconnected-(U2-PadA2)") (class "Default")
      (node (ref "U2") (pin "A2") (pinfunction "A2_A2") (pintype "bidirectional"))
    )
    (net (code "142") (name "unconnected-(U2-PadA3)") (class "Default")
      (node (ref "U2") (pin "A3") (pinfunction "A3_A3") (pintype "bidirectional"))
    )
    (net (code "143") (name "unconnected-(U2-PadA4)") (class "Default")
      (node (ref "U2") (pin "A4") (pinfunction "A4_A4") (pintype "bidirectional"))
    )
    (net (code "144") (name "unconnected-(U2-PadA5)") (class "Default")
      (node (ref "U2") (pin "A5") (pinfunction "A5_A5") (pintype "bidirectional"))
    )
    (net (code "145") (name "unconnected-(U2-PadA6)") (class "Default")
      (node (ref "U2") (pin "A6") (pinfunction "A6_A6") (pintype "bidirectional"))
    )
    (net (code "146") (name "unconnected-(U2-PadA7)") (class "Default")
      (node (ref "U2") (pin "A7") (pinfunction "A7_A7") (pintype "bidirectional"))
    )
    (net (code "147") (name "unconnected-(U2-PadA8)") (class "Default")
      (node (ref "U2") (pin "A8") (pinfunction "A8_A8") (pintype "bidirectional"))
    )
    (net (code "148") (name "unconnected-(U2-PadA9)") (class "Default")
      (node (ref "U2") (pin "A9") (pinfunction "A9_A9") (pintype "bidirectional"))
    )
    (net (code "149") (name "unconnected-(U2-PadA10)") (class "Default")
      (node (ref "U2") (pin "A10") (pinfunction "A10_A10") (pintype "bidirectional"))
    )
    (net (code "150") (name "unconnected-(U2-PadA11)") (class "Default")
      (node (ref "U2") (pin "A11") (pinfunction "A11_A11") (pintype "bidirectional"))
    )
    (net (code "151") (name "unconnected-(U2-PadA12)") (class "Default")
      (node (ref "U2") (pin "A12") (pinfunction "A12_A12") (pintype "bidirectional"))
    )
    (net (code "152") (name "unconnected-(U2-PadA13)") (class "Default")
      (node (ref "U2") (pin "A13") (pinfunction "A13_A13") (pintype "bidirectional"))
    )
    (net (code "153") (name "unconnected-(U2-PadA14)") (class "Default")
      (node (ref "U2") (pin "A14") (pinfunction "A14_A14") (pintype "bidirectional"))
    )
    (net (code "154") (name "unconnected-(U2-PadA15)") (class "Default")
      (node (ref "U2") (pin "A15") (pinfunction "A15_A15") (pintype "bidirectional"))
    )
    (net (code "155") (name "unconnected-(U2-PadAREF)") (class "Default")
      (node (ref "U2") (pin "AREF") (pinfunction "AREF_AREF") (pintype "bidirectional"))
    )
    (net (code "156") (name "unconnected-(U2-PadVIN)") (class "Default")
      (node (ref "U2") (pin "VIN") (pinfunction "VIN_VIN") (pintype "bidirectional"))
    )
    (net (code "157") (name "unconnected-(U5-O1-Pad16)") (class "Default")
      (node (ref "U5") (pin "16") (pinfunction "O1_16") (pintype "open_collector"))
    )
    (net (code "158") (name "unconnected-(U5-O2-Pad15)") (class "Default")
      (node (ref "U5") (pin "15") (pinfunction "O2_15") (pintype "open_collector"))
    )
    (net (code "159") (name "unconnected-(U5-O3-Pad14)") (class "Default")
      (node (ref "U5") (pin "14") (pinfunction "O3_14") (pintype "open_collector"))
    )
    (net (code "160") (name "unconnected-(U5-O4-Pad13)") (class "Default")
      (node (ref "U5") (pin "13") (pinfunction "O4_13") (pintype "open_collector"))
    )
    (net (code "161") (name "unconnected-(U5-O5-Pad12)") (class "Default")
      (node (ref "U5") (pin "12") (pinfunction "O5_12") (pintype "open_collector"))
    )
    (net (code "162") (name "unconnected-(U5-O6-Pad11)") (class "Default")
      (node (ref "U5") (pin "11") (pinfunction "O6_11") (pintype "open_collector"))
    )
    (net (code "163") (name "unconnected-(U5-O7-Pad10)") (class "Default")
      (node (ref "U5") (pin "10") (pinfunction "O7_10") (pintype "open_collector"))
    )
    (net (code "164") (name "unconnected-(U6-O1-Pad16)") (class "Default")
      (node (ref "U6") (pin "16") (pinfunction "O1_16") (pintype "open_collector"))
    )
    (net (code "165") (name "unconnected-(U6-O2-Pad15)") (class "Default")
      (node (ref "U6") (pin "15") (pinfunction "O2_15") (pintype "open_collector"))
    )
    (net (code "166") (name "unconnected-(U6-O3-Pad14)") (class "Default")
      (node (ref "U6") (pin "14") (pinfunction "O3_14") (pintype "open_collector"))
    )
    (net (code "167") (name "unconnected-(U6-O4-Pad13)") (class "Default")
      (node (ref "U6") (pin "13") (pinfunction "O4_13") (pintype "open_collector"))
    )
    (net (code "168") (name "unconnected-(U6-O5-Pad12)") (class "Default")
      (node (ref "U6") (pin "12") (pinfunction "O5_12") (pintype "open_collector"))
    )
    (net (code "169") (name "unconnected-(U6-O6-Pad11)") (class "Default")
      (node (ref "U6") (pin "11") (pinfunction "O6_11") (pintype "open_collector"))
    )
    (net (code "170") (name "unconnected-(U6-O7-Pad10)") (class "Default")
      (node (ref "U6") (pin "10") (pinfunction "O7_10") (pintype "open_collector"))
    )
  )
)
